# sensors.net
KiCad netlist of a schematic drawn in Altium Designer
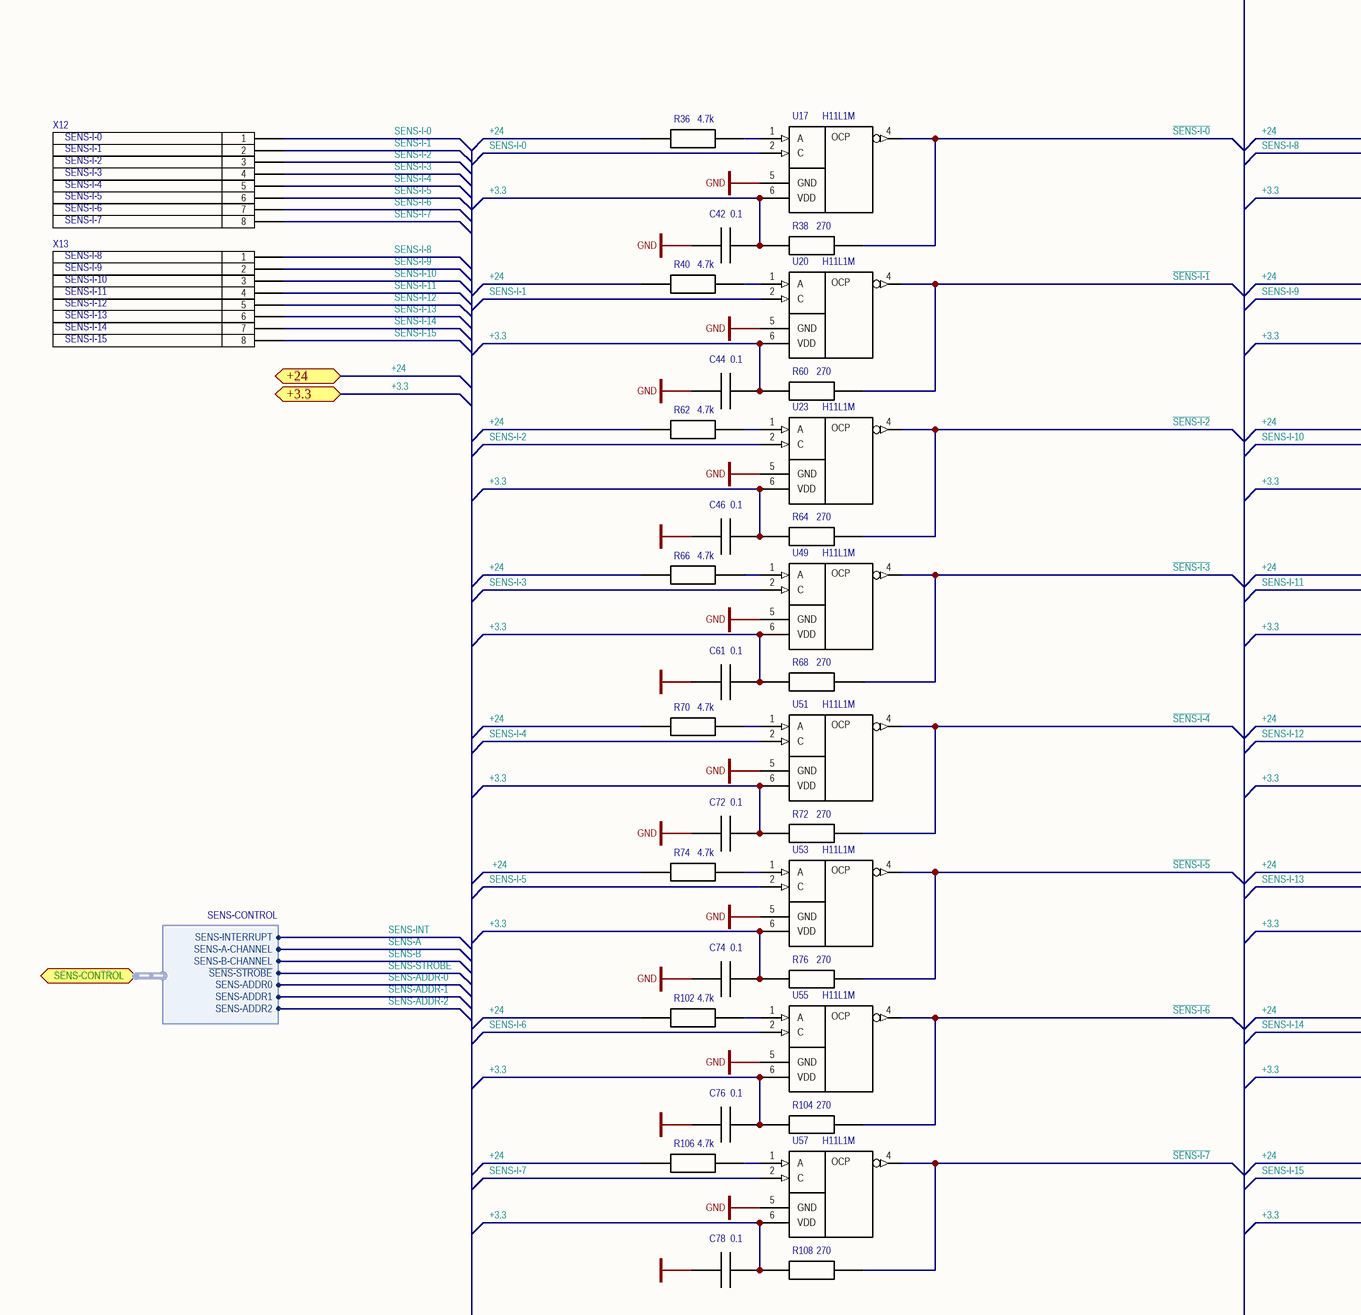
[diagram p0: sensors.SchDoc, top left]
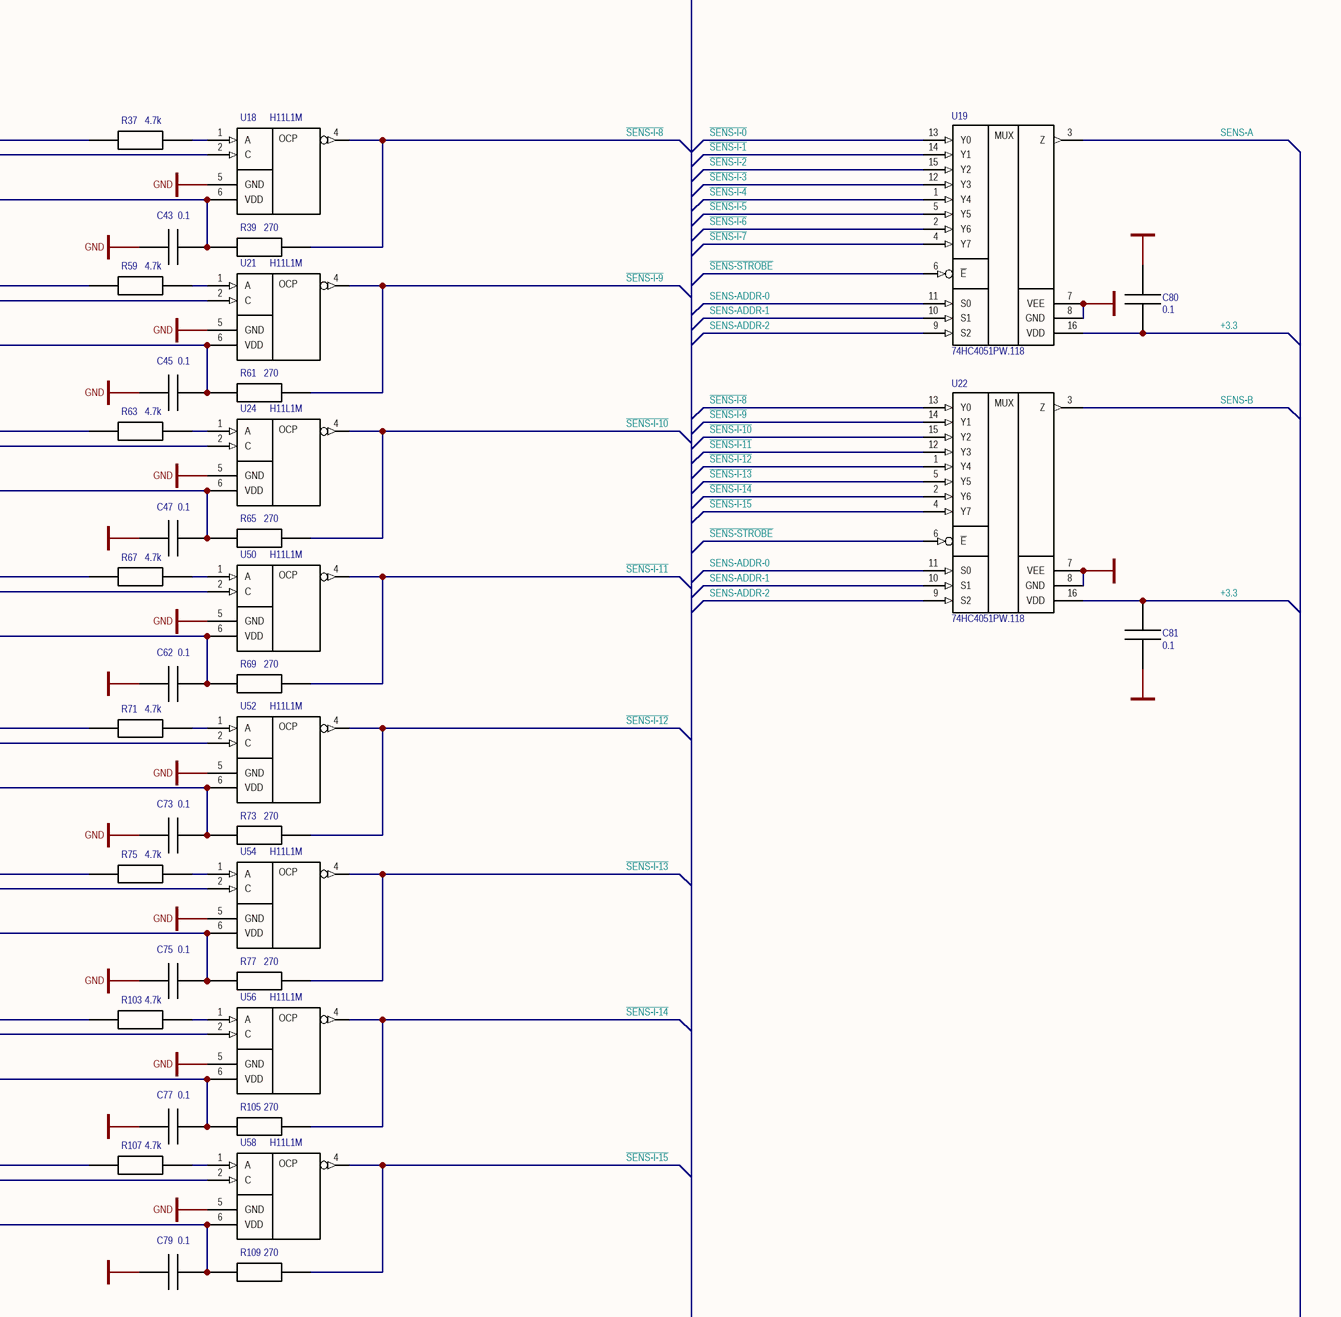
[diagram p1: sensors.SchDoc, top right]
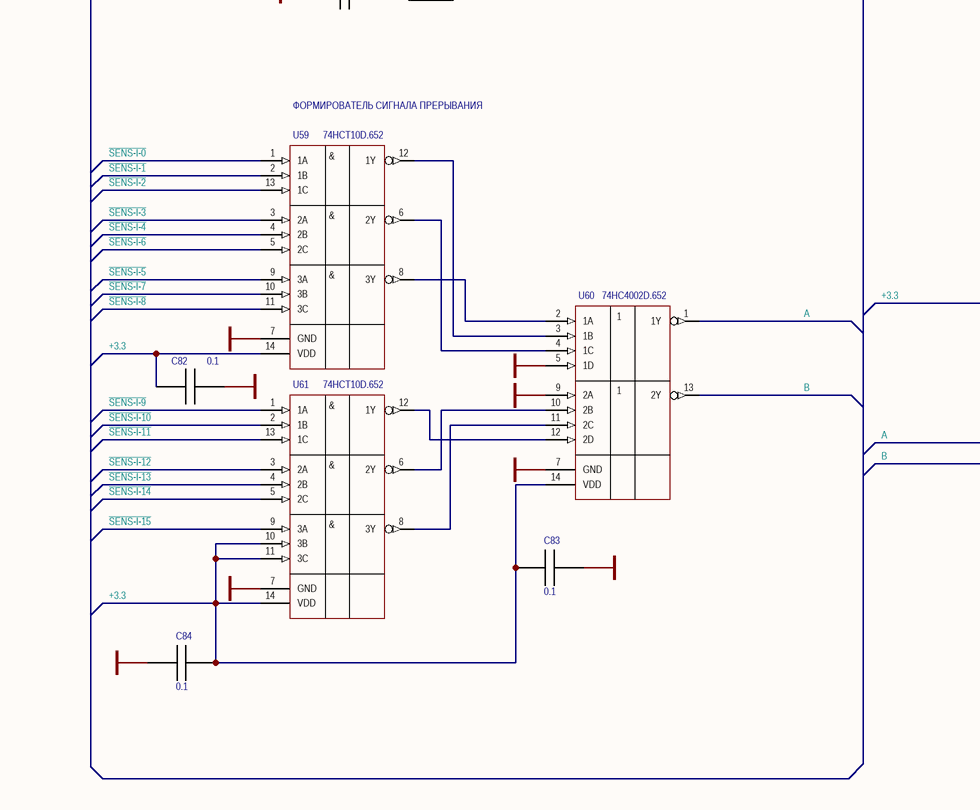
[diagram p2: sensors.SchDoc, bottom left]
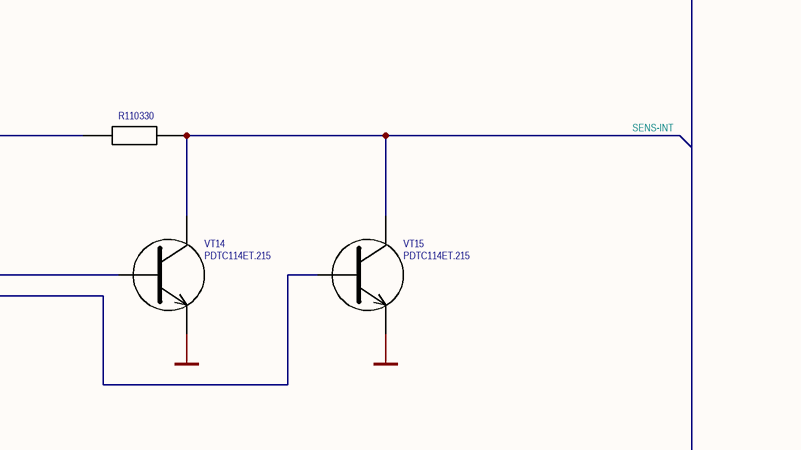
[diagram p3: sensors.SchDoc, bottom right]

(export (version "E")
  (design (tool "Eeschema 10.0.6"))
  (components
    (comp (ref "C42")
      (value "0.1")
      (footprint "CAPC2012X04N")
      (description "SMD конденсатор")
      (libsource (lib "ulysses_library") (part "C"))
    )
    (comp (ref "C43")
      (value "0.1")
      (footprint "CAPC2012X04N")
      (description "SMD конденсатор")
      (libsource (lib "ulysses_library") (part "C"))
    )
    (comp (ref "C44")
      (value "0.1")
      (footprint "CAPC2012X04N")
      (description "SMD конденсатор")
      (libsource (lib "ulysses_library") (part "C"))
    )
    (comp (ref "C45")
      (value "0.1")
      (footprint "CAPC2012X04N")
      (description "SMD конденсатор")
      (libsource (lib "ulysses_library") (part "C"))
    )
    (comp (ref "C46")
      (value "0.1")
      (footprint "CAPC2012X04N")
      (description "SMD конденсатор")
      (libsource (lib "ulysses_library") (part "C"))
    )
    (comp (ref "C47")
      (value "0.1")
      (footprint "CAPC2012X04N")
      (description "SMD конденсатор")
      (libsource (lib "ulysses_library") (part "C"))
    )
    (comp (ref "C61")
      (value "0.1")
      (footprint "CAPC2012X04N")
      (description "SMD конденсатор")
      (libsource (lib "ulysses_library") (part "C"))
    )
    (comp (ref "C62")
      (value "0.1")
      (footprint "CAPC2012X04N")
      (description "SMD конденсатор")
      (libsource (lib "ulysses_library") (part "C"))
    )
    (comp (ref "C72")
      (value "0.1")
      (footprint "CAPC2012X04N")
      (description "SMD конденсатор")
      (libsource (lib "ulysses_library") (part "C"))
    )
    (comp (ref "C73")
      (value "0.1")
      (footprint "CAPC2012X04N")
      (description "SMD конденсатор")
      (libsource (lib "ulysses_library") (part "C"))
    )
    (comp (ref "C74")
      (value "0.1")
      (footprint "CAPC2012X04N")
      (description "SMD конденсатор")
      (libsource (lib "ulysses_library") (part "C"))
    )
    (comp (ref "C75")
      (value "0.1")
      (footprint "CAPC2012X04N")
      (description "SMD конденсатор")
      (libsource (lib "ulysses_library") (part "C"))
    )
    (comp (ref "C76")
      (value "0.1")
      (footprint "CAPC2012X04N")
      (description "SMD конденсатор")
      (libsource (lib "ulysses_library") (part "C"))
    )
    (comp (ref "C77")
      (value "0.1")
      (footprint "CAPC2012X04N")
      (description "SMD конденсатор")
      (libsource (lib "ulysses_library") (part "C"))
    )
    (comp (ref "C78")
      (value "0.1")
      (footprint "CAPC2012X04N")
      (description "SMD конденсатор")
      (libsource (lib "ulysses_library") (part "C"))
    )
    (comp (ref "C79")
      (value "0.1")
      (footprint "CAPC2012X04N")
      (description "SMD конденсатор")
      (libsource (lib "ulysses_library") (part "C"))
    )
    (comp (ref "C80")
      (value "0.1")
      (footprint "CAPC2012X04N")
      (description "SMD конденсатор")
      (libsource (lib "ulysses_library") (part "C"))
    )
    (comp (ref "C81")
      (value "0.1")
      (footprint "CAPC2012X04N")
      (description "SMD конденсатор")
      (libsource (lib "") (part "C_1"))
    )
    (comp (ref "C82")
      (value "0.1")
      (footprint "CAPC2012X04N")
      (description "SMD конденсатор")
      (libsource (lib "ulysses_library") (part "C"))
    )
    (comp (ref "C83")
      (value "0.1")
      (footprint "CAPC2012X04N")
      (description "SMD конденсатор")
      (libsource (lib "ulysses_library") (part "C"))
    )
    (comp (ref "C84")
      (value "0.1")
      (footprint "CAPC2012X04N")
      (description "SMD конденсатор")
      (libsource (lib "ulysses_library") (part "C"))
    )
    (comp (ref "R36")
      (value "4.7k")
      (footprint "RESC2012X04N")
      (description "SMD резистор")
      (libsource (lib "") (part "R_1"))
    )
    (comp (ref "R37")
      (value "4.7k")
      (footprint "RESC2012X04N")
      (description "SMD резистор")
      (libsource (lib "ulysses_library") (part "R"))
    )
    (comp (ref "R38")
      (value "270")
      (footprint "RESC2012X04N")
      (description "SMD резистор")
      (libsource (lib "") (part "R_1"))
    )
    (comp (ref "R39")
      (value "270")
      (footprint "RESC2012X04N")
      (description "SMD резистор")
      (libsource (lib "") (part "R_1"))
    )
    (comp (ref "R40")
      (value "4.7k")
      (footprint "RESC2012X04N")
      (description "SMD резистор")
      (libsource (lib "") (part "R_1"))
    )
    (comp (ref "R59")
      (value "4.7k")
      (footprint "RESC2012X04N")
      (description "SMD резистор")
      (libsource (lib "ulysses_library") (part "R"))
    )
    (comp (ref "R60")
      (value "270")
      (footprint "RESC2012X04N")
      (description "SMD резистор")
      (libsource (lib "") (part "R_1"))
    )
    (comp (ref "R61")
      (value "270")
      (footprint "RESC2012X04N")
      (description "SMD резистор")
      (libsource (lib "") (part "R_1"))
    )
    (comp (ref "R62")
      (value "4.7k")
      (footprint "RESC2012X04N")
      (description "SMD резистор")
      (libsource (lib "") (part "R_1"))
    )
    (comp (ref "R63")
      (value "4.7k")
      (footprint "RESC2012X04N")
      (description "SMD резистор")
      (libsource (lib "ulysses_library") (part "R"))
    )
    (comp (ref "R64")
      (value "270")
      (footprint "RESC2012X04N")
      (description "SMD резистор")
      (libsource (lib "") (part "R_1"))
    )
    (comp (ref "R65")
      (value "270")
      (footprint "RESC2012X04N")
      (description "SMD резистор")
      (libsource (lib "") (part "R_1"))
    )
    (comp (ref "R66")
      (value "4.7k")
      (footprint "RESC2012X04N")
      (description "SMD резистор")
      (libsource (lib "") (part "R_1"))
    )
    (comp (ref "R67")
      (value "4.7k")
      (footprint "RESC2012X04N")
      (description "SMD резистор")
      (libsource (lib "ulysses_library") (part "R"))
    )
    (comp (ref "R68")
      (value "270")
      (footprint "RESC2012X04N")
      (description "SMD резистор")
      (libsource (lib "") (part "R_1"))
    )
    (comp (ref "R69")
      (value "270")
      (footprint "RESC2012X04N")
      (description "SMD резистор")
      (libsource (lib "") (part "R_1"))
    )
    (comp (ref "R70")
      (value "4.7k")
      (footprint "RESC2012X04N")
      (description "SMD резистор")
      (libsource (lib "") (part "R_1"))
    )
    (comp (ref "R71")
      (value "4.7k")
      (footprint "RESC2012X04N")
      (description "SMD резистор")
      (libsource (lib "ulysses_library") (part "R"))
    )
    (comp (ref "R72")
      (value "270")
      (footprint "RESC2012X04N")
      (description "SMD резистор")
      (libsource (lib "") (part "R_1"))
    )
    (comp (ref "R73")
      (value "270")
      (footprint "RESC2012X04N")
      (description "SMD резистор")
      (libsource (lib "") (part "R_1"))
    )
    (comp (ref "R74")
      (value "4.7k")
      (footprint "RESC2012X04N")
      (description "SMD резистор")
      (libsource (lib "") (part "R_1"))
    )
    (comp (ref "R75")
      (value "4.7k")
      (footprint "RESC2012X04N")
      (description "SMD резистор")
      (libsource (lib "ulysses_library") (part "R"))
    )
    (comp (ref "R76")
      (value "270")
      (footprint "RESC2012X04N")
      (description "SMD резистор")
      (libsource (lib "") (part "R_1"))
    )
    (comp (ref "R77")
      (value "270")
      (footprint "RESC2012X04N")
      (description "SMD резистор")
      (libsource (lib "") (part "R_1"))
    )
    (comp (ref "R102")
      (value "4.7k")
      (footprint "RESC2012X04N")
      (description "SMD резистор")
      (libsource (lib "") (part "R_1"))
    )
    (comp (ref "R103")
      (value "4.7k")
      (footprint "RESC2012X04N")
      (description "SMD резистор")
      (libsource (lib "ulysses_library") (part "R"))
    )
    (comp (ref "R104")
      (value "270")
      (footprint "RESC2012X04N")
      (description "SMD резистор")
      (libsource (lib "") (part "R_1"))
    )
    (comp (ref "R105")
      (value "270")
      (footprint "RESC2012X04N")
      (description "SMD резистор")
      (libsource (lib "") (part "R_1"))
    )
    (comp (ref "R106")
      (value "4.7k")
      (footprint "RESC2012X04N")
      (description "SMD резистор")
      (libsource (lib "") (part "R_1"))
    )
    (comp (ref "R107")
      (value "4.7k")
      (footprint "RESC2012X04N")
      (description "SMD резистор")
      (libsource (lib "ulysses_library") (part "R"))
    )
    (comp (ref "R108")
      (value "270")
      (footprint "RESC2012X04N")
      (description "SMD резистор")
      (libsource (lib "") (part "R_1"))
    )
    (comp (ref "R109")
      (value "270")
      (footprint "RESC2012X04N")
      (description "SMD резистор")
      (libsource (lib "") (part "R_1"))
    )
    (comp (ref "R110")
      (value "330")
      (footprint "RESC3216X05N")
      (description "SMD резистор")
      (libsource (lib "ulysses_library") (part "R"))
    )
    (comp (ref "U17")
      (value "H11L1M")
      (footprint "DIP6")
      (description "Fairchild H11L1M Schmitt Trigger Output Optocoupler")
      (libsource (lib "") (part "H11L1M_1"))
    )
    (comp (ref "U18")
      (value "H11L1M")
      (footprint "DIP6")
      (description "Fairchild H11L1M Schmitt Trigger Output Optocoupler")
      (libsource (lib "") (part "H11L1M_1"))
    )
    (comp (ref "U19")
      (value "74HC4051PW.118")
      (footprint "TSOP65P640X120-16N")
      (libsource (lib "ulysses_library") (part "74HC4051PW.118"))
    )
    (comp (ref "U20")
      (value "H11L1M")
      (footprint "DIP6")
      (description "Fairchild H11L1M Schmitt Trigger Output Optocoupler")
      (libsource (lib "") (part "H11L1M_1"))
    )
    (comp (ref "U21")
      (value "H11L1M")
      (footprint "DIP6")
      (description "Fairchild H11L1M Schmitt Trigger Output Optocoupler")
      (libsource (lib "") (part "H11L1M_1"))
    )
    (comp (ref "U22")
      (value "74HC4051PW.118")
      (footprint "TSOP65P640X120-16N")
      (libsource (lib "ulysses_library") (part "74HC4051PW.118"))
    )
    (comp (ref "U23")
      (value "H11L1M")
      (footprint "DIP6")
      (description "Fairchild H11L1M Schmitt Trigger Output Optocoupler")
      (libsource (lib "") (part "H11L1M_1"))
    )
    (comp (ref "U24")
      (value "H11L1M")
      (footprint "DIP6")
      (description "Fairchild H11L1M Schmitt Trigger Output Optocoupler")
      (libsource (lib "") (part "H11L1M_1"))
    )
    (comp (ref "U49")
      (value "H11L1M")
      (footprint "DIP6")
      (description "Fairchild H11L1M Schmitt Trigger Output Optocoupler")
      (libsource (lib "ulysses_library") (part "H11L1M"))
    )
    (comp (ref "U50")
      (value "H11L1M")
      (footprint "DIP6")
      (description "Fairchild H11L1M Schmitt Trigger Output Optocoupler")
      (libsource (lib "ulysses_library") (part "H11L1M"))
    )
    (comp (ref "U51")
      (value "H11L1M")
      (footprint "DIP6")
      (description "Fairchild H11L1M Schmitt Trigger Output Optocoupler")
      (libsource (lib "") (part "H11L1M_1"))
    )
    (comp (ref "U52")
      (value "H11L1M")
      (footprint "DIP6")
      (description "Fairchild H11L1M Schmitt Trigger Output Optocoupler")
      (libsource (lib "") (part "H11L1M_1"))
    )
    (comp (ref "U53")
      (value "H11L1M")
      (footprint "DIP6")
      (description "Fairchild H11L1M Schmitt Trigger Output Optocoupler")
      (libsource (lib "") (part "H11L1M_1"))
    )
    (comp (ref "U54")
      (value "H11L1M")
      (footprint "DIP6")
      (description "Fairchild H11L1M Schmitt Trigger Output Optocoupler")
      (libsource (lib "") (part "H11L1M_1"))
    )
    (comp (ref "U55")
      (value "H11L1M")
      (footprint "DIP6")
      (description "Fairchild H11L1M Schmitt Trigger Output Optocoupler")
      (libsource (lib "") (part "H11L1M_1"))
    )
    (comp (ref "U56")
      (value "H11L1M")
      (footprint "DIP6")
      (description "Fairchild H11L1M Schmitt Trigger Output Optocoupler")
      (libsource (lib "") (part "H11L1M_1"))
    )
    (comp (ref "U57")
      (value "H11L1M")
      (footprint "DIP6")
      (description "Fairchild H11L1M Schmitt Trigger Output Optocoupler")
      (libsource (lib "") (part "H11L1M_1"))
    )
    (comp (ref "U58")
      (value "H11L1M")
      (footprint "DIP6")
      (description "Fairchild H11L1M Schmitt Trigger Output Optocoupler")
      (libsource (lib "") (part "H11L1M_1"))
    )
    (comp (ref "U59")
      (value "74HCT10D.652")
      (footprint "SOIC127P600X175-14N")
      (libsource (lib "ulysses_library") (part "74HCT10D.652"))
    )
    (comp (ref "U60")
      (value "74HC4002D.652")
      (footprint "SOIC127P600X175-14N")
      (libsource (lib "ulysses_library") (part "74HC4002D.652"))
    )
    (comp (ref "U61")
      (value "74HCT10D.652")
      (footprint "SOIC127P600X175-14N")
      (libsource (lib "ulysses_library") (part "74HCT10D.652"))
    )
    (comp (ref "VT14")
      (value "PDTC114ET.215")
      (footprint "SOT95P238X102-3N")
      (description "NPN transistor with bias circuit")
      (libsource (lib "ulysses_library") (part "PDTC114ET.215"))
    )
    (comp (ref "VT15")
      (value "PDTC114ET.215")
      (footprint "SOT95P238X102-3N")
      (description "NPN transistor with bias circuit")
      (libsource (lib "") (part "PDTC114ET.215_1"))
    )
    (comp (ref "X12")
      (value "MINI-FIT-8-WAY-M")
      (footprint "MINI-FIT-8-WAY-SM")
      (libsource (lib "ulysses_library") (part "MINI-FIT-8-WAY-M"))
    )
    (comp (ref "X13")
      (value "MINI-FIT-8-WAY-M")
      (footprint "MINI-FIT-8-WAY-SM")
      (libsource (lib "ulysses_library") (part "MINI-FIT-8-WAY-M"))
    )
  )
  (nets
    (net (code "2") (name "/+3.3") (class "Default")
      (node (ref "C42") (pin "2") (pinfunction "2_2") (pintype "passive"))
      (node (ref "C43") (pin "2") (pinfunction "2_2") (pintype "passive"))
      (node (ref "C44") (pin "2") (pinfunction "2_2") (pintype "passive"))
      (node (ref "C45") (pin "2") (pinfunction "2_2") (pintype "passive"))
      (node (ref "C46") (pin "2") (pinfunction "2_2") (pintype "passive"))
      (node (ref "C47") (pin "2") (pinfunction "2_2") (pintype "passive"))
      (node (ref "C61") (pin "2") (pinfunction "2_2") (pintype "passive"))
      (node (ref "C62") (pin "2") (pinfunction "2_2") (pintype "passive"))
      (node (ref "C72") (pin "2") (pinfunction "2_2") (pintype "passive"))
      (node (ref "C73") (pin "2") (pinfunction "2_2") (pintype "passive"))
      (node (ref "C74") (pin "2") (pinfunction "2_2") (pintype "passive"))
      (node (ref "C75") (pin "2") (pinfunction "2_2") (pintype "passive"))
      (node (ref "C76") (pin "2") (pinfunction "2_2") (pintype "passive"))
      (node (ref "C77") (pin "2") (pinfunction "2_2") (pintype "passive"))
      (node (ref "C78") (pin "2") (pinfunction "2_2") (pintype "passive"))
      (node (ref "C79") (pin "2") (pinfunction "2_2") (pintype "passive"))
      (node (ref "C80") (pin "1") (pinfunction "1_1") (pintype "passive"))
      (node (ref "C81") (pin "2") (pinfunction "2_2") (pintype "passive"))
      (node (ref "C82") (pin "1") (pinfunction "1_1") (pintype "passive"))
      (node (ref "C83") (pin "1") (pinfunction "1_1") (pintype "passive"))
      (node (ref "C84") (pin "2") (pinfunction "2_2") (pintype "passive"))
      (node (ref "R104") (pin "1") (pintype "passive"))
      (node (ref "R105") (pin "1") (pintype "passive"))
      (node (ref "R108") (pin "1") (pintype "passive"))
      (node (ref "R109") (pin "1") (pintype "passive"))
      (node (ref "R110") (pin "1") (pintype "passive"))
      (node (ref "R38") (pin "1") (pintype "passive"))
      (node (ref "R39") (pin "1") (pintype "passive"))
      (node (ref "R60") (pin "1") (pintype "passive"))
      (node (ref "R61") (pin "1") (pintype "passive"))
      (node (ref "R64") (pin "1") (pintype "passive"))
      (node (ref "R65") (pin "1") (pintype "passive"))
      (node (ref "R68") (pin "1") (pintype "passive"))
      (node (ref "R69") (pin "1") (pintype "passive"))
      (node (ref "R72") (pin "1") (pintype "passive"))
      (node (ref "R73") (pin "1") (pintype "passive"))
      (node (ref "R76") (pin "1") (pintype "passive"))
      (node (ref "R77") (pin "1") (pintype "passive"))
      (node (ref "U17") (pin "6") (pinfunction "VDD_6") (pintype "power_in"))
      (node (ref "U18") (pin "6") (pinfunction "VDD_6") (pintype "power_in"))
      (node (ref "U19") (pin "16") (pinfunction "VDD_16") (pintype "power_in"))
      (node (ref "U20") (pin "6") (pinfunction "VDD_6") (pintype "power_in"))
      (node (ref "U21") (pin "6") (pinfunction "VDD_6") (pintype "power_in"))
      (node (ref "U22") (pin "16") (pinfunction "VDD_16") (pintype "power_in"))
      (node (ref "U23") (pin "6") (pinfunction "VDD_6") (pintype "power_in"))
      (node (ref "U24") (pin "6") (pinfunction "VDD_6") (pintype "power_in"))
      (node (ref "U49") (pin "6") (pinfunction "VDD_6") (pintype "power_in"))
      (node (ref "U50") (pin "6") (pinfunction "VDD_6") (pintype "power_in"))
      (node (ref "U51") (pin "6") (pinfunction "VDD_6") (pintype "power_in"))
      (node (ref "U52") (pin "6") (pinfunction "VDD_6") (pintype "power_in"))
      (node (ref "U53") (pin "6") (pinfunction "VDD_6") (pintype "power_in"))
      (node (ref "U54") (pin "6") (pinfunction "VDD_6") (pintype "power_in"))
      (node (ref "U55") (pin "6") (pinfunction "VDD_6") (pintype "power_in"))
      (node (ref "U56") (pin "6") (pinfunction "VDD_6") (pintype "power_in"))
      (node (ref "U57") (pin "6") (pinfunction "VDD_6") (pintype "power_in"))
      (node (ref "U58") (pin "6") (pinfunction "VDD_6") (pintype "power_in"))
      (node (ref "U59") (pin "14") (pinfunction "VDD_14") (pintype "power_in"))
      (node (ref "U60") (pin "14") (pinfunction "VDD_14") (pintype "power_in"))
      (node (ref "U61") (pin "10") (pinfunction "3B_10") (pintype "input"))
      (node (ref "U61") (pin "11") (pinfunction "3C_11") (pintype "input"))
      (node (ref "U61") (pin "14") (pinfunction "VDD_14") (pintype "power_in"))
    )
    (net (code "3") (name "/+24") (class "Default")
      (node (ref "R102") (pin "1") (pintype "passive"))
      (node (ref "R103") (pin "1") (pintype "passive"))
      (node (ref "R106") (pin "1") (pintype "passive"))
      (node (ref "R107") (pin "1") (pintype "passive"))
      (node (ref "R36") (pin "1") (pintype "passive"))
      (node (ref "R37") (pin "1") (pintype "passive"))
      (node (ref "R40") (pin "1") (pintype "passive"))
      (node (ref "R59") (pin "1") (pintype "passive"))
      (node (ref "R62") (pin "1") (pintype "passive"))
      (node (ref "R63") (pin "1") (pintype "passive"))
      (node (ref "R66") (pin "1") (pintype "passive"))
      (node (ref "R67") (pin "1") (pintype "passive"))
      (node (ref "R70") (pin "1") (pintype "passive"))
      (node (ref "R71") (pin "1") (pintype "passive"))
      (node (ref "R74") (pin "1") (pintype "passive"))
      (node (ref "R75") (pin "1") (pintype "passive"))
    )
    (net (code "4") (name "/A") (class "Default")
      (node (ref "U60") (pin "1") (pinfunction "1Y_1") (pintype "output"))
      (node (ref "VT14") (pin "1") (pinfunction "B_1") (pintype "power_in"))
    )
    (net (code "5") (name "/B") (class "Default")
      (node (ref "U60") (pin "13") (pinfunction "2Y_13") (pintype "output"))
      (node (ref "VT15") (pin "1") (pinfunction "B_1") (pintype "power_in"))
    )
    (net (code "6") (name "/SENS-A") (class "Default")
      (node (ref "U19") (pin "3") (pinfunction "Z_3") (pintype "output"))
    )
    (net (code "7") (name "/SENS-ADDR-0") (class "Default")
      (node (ref "U19") (pin "11") (pinfunction "S0_11") (pintype "input"))
      (node (ref "U22") (pin "11") (pinfunction "S0_11") (pintype "input"))
    )
    (net (code "8") (name "/SENS-ADDR-1") (class "Default")
      (node (ref "U19") (pin "10") (pinfunction "S1_10") (pintype "input"))
      (node (ref "U22") (pin "10") (pinfunction "S1_10") (pintype "input"))
    )
    (net (code "9") (name "/SENS-ADDR-2") (class "Default")
      (node (ref "U19") (pin "9") (pinfunction "S2_9") (pintype "input"))
      (node (ref "U22") (pin "9") (pinfunction "S2_9") (pintype "input"))
    )
    (net (code "10") (name "/SENS-B") (class "Default")
      (node (ref "U22") (pin "3") (pinfunction "Z_3") (pintype "output"))
    )
    (net (code "11") (name "/SENS-I-0") (class "Default")
      (node (ref "U17") (pin "2") (pinfunction "C_2") (pintype "input"))
      (node (ref "X12") (pin "1") (pinfunction "1_1") (pintype "passive"))
    )
    (net (code "12") (name "/SENS-I-1") (class "Default")
      (node (ref "U20") (pin "2") (pinfunction "C_2") (pintype "input"))
      (node (ref "X12") (pin "2") (pinfunction "2_2") (pintype "passive"))
    )
    (net (code "13") (name "/SENS-I-2") (class "Default")
      (node (ref "U23") (pin "2") (pinfunction "C_2") (pintype "input"))
      (node (ref "X12") (pin "3") (pinfunction "3_3") (pintype "passive"))
    )
    (net (code "14") (name "/SENS-I-3") (class "Default")
      (node (ref "U49") (pin "2") (pinfunction "C_2") (pintype "input"))
      (node (ref "X12") (pin "4") (pinfunction "4_4") (pintype "passive"))
    )
    (net (code "15") (name "/SENS-I-4") (class "Default")
      (node (ref "U51") (pin "2") (pinfunction "C_2") (pintype "input"))
      (node (ref "X12") (pin "5") (pinfunction "5_5") (pintype "passive"))
    )
    (net (code "16") (name "/SENS-I-5") (class "Default")
      (node (ref "U53") (pin "2") (pinfunction "C_2") (pintype "input"))
      (node (ref "X12") (pin "6") (pinfunction "6_6") (pintype "passive"))
    )
    (net (code "17") (name "/SENS-I-6") (class "Default")
      (node (ref "U55") (pin "2") (pinfunction "C_2") (pintype "input"))
      (node (ref "X12") (pin "7") (pinfunction "7_7") (pintype "passive"))
    )
    (net (code "18") (name "/SENS-I-7") (class "Default")
      (node (ref "U57") (pin "2") (pinfunction "C_2") (pintype "input"))
      (node (ref "X12") (pin "8") (pinfunction "8_8") (pintype "passive"))
    )
    (net (code "19") (name "/SENS-I-8") (class "Default")
      (node (ref "U18") (pin "2") (pinfunction "C_2") (pintype "input"))
      (node (ref "X13") (pin "1") (pinfunction "1_1") (pintype "passive"))
    )
    (net (code "20") (name "/SENS-I-9") (class "Default")
      (node (ref "U21") (pin "2") (pinfunction "C_2") (pintype "input"))
      (node (ref "X13") (pin "2") (pinfunction "2_2") (pintype "passive"))
    )
    (net (code "21") (name "/SENS-I-10") (class "Default")
      (node (ref "U24") (pin "2") (pinfunction "C_2") (pintype "input"))
      (node (ref "X13") (pin "3") (pinfunction "3_3") (pintype "passive"))
    )
    (net (code "22") (name "/SENS-I-11") (class "Default")
      (node (ref "U50") (pin "2") (pinfunction "C_2") (pintype "input"))
      (node (ref "X13") (pin "4") (pinfunction "4_4") (pintype "passive"))
    )
    (net (code "23") (name "/SENS-I-12") (class "Default")
      (node (ref "U52") (pin "2") (pinfunction "C_2") (pintype "input"))
      (node (ref "X13") (pin "5") (pinfunction "5_5") (pintype "passive"))
    )
    (net (code "24") (name "/SENS-I-13") (class "Default")
      (node (ref "U54") (pin "2") (pinfunction "C_2") (pintype "input"))
      (node (ref "X13") (pin "6") (pinfunction "6_6") (pintype "passive"))
    )
    (net (code "25") (name "/SENS-I-14") (class "Default")
      (node (ref "U56") (pin "2") (pinfunction "C_2") (pintype "input"))
      (node (ref "X13") (pin "7") (pinfunction "7_7") (pintype "passive"))
    )
    (net (code "26") (name "/SENS-I-15") (class "Default")
      (node (ref "U58") (pin "2") (pinfunction "C_2") (pintype "input"))
      (node (ref "X13") (pin "8") (pinfunction "8_8") (pintype "passive"))
    )
    (net (code "27") (name "/SENS-INT") (class "Default")
      (node (ref "R110") (pin "2") (pinfunction "2_2") (pintype "passive"))
      (node (ref "VT14") (pin "3") (pinfunction "C_3") (pintype "power_in"))
      (node (ref "VT15") (pin "3") (pinfunction "C_3") (pintype "power_in"))
    )
    (net (code "29") (name "/~{SENS-I-0}") (class "Default")
      (node (ref "R38") (pin "2") (pinfunction "2_2") (pintype "passive"))
      (node (ref "U17") (pin "4") (pinfunction "OUT_4") (pintype "output"))
      (node (ref "U19") (pin "13") (pinfunction "Y0_13") (pintype "input"))
      (node (ref "U59") (pin "1") (pinfunction "1A_1") (pintype "input"))
    )
    (net (code "30") (name "/~{SENS-I-1}") (class "Default")
      (node (ref "R60") (pin "2") (pinfunction "2_2") (pintype "passive"))
      (node (ref "U19") (pin "14") (pinfunction "Y1_14") (pintype "input"))
      (node (ref "U20") (pin "4") (pinfunction "OUT_4") (pintype "output"))
      (node (ref "U59") (pin "2") (pinfunction "1B_2") (pintype "input"))
    )
    (net (code "31") (name "/~{SENS-I-2}") (class "Default")
      (node (ref "R64") (pin "2") (pinfunction "2_2") (pintype "passive"))
      (node (ref "U19") (pin "15") (pinfunction "Y2_15") (pintype "input"))
      (node (ref "U23") (pin "4") (pinfunction "OUT_4") (pintype "output"))
      (node (ref "U59") (pin "13") (pinfunction "1C_13") (pintype "input"))
    )
    (net (code "32") (name "/~{SENS-I-3}") (class "Default")
      (node (ref "R68") (pin "2") (pinfunction "2_2") (pintype "passive"))
      (node (ref "U19") (pin "12") (pinfunction "Y3_12") (pintype "input"))
      (node (ref "U49") (pin "4") (pinfunction "OUT_4") (pintype "output"))
      (node (ref "U59") (pin "3") (pinfunction "2A_3") (pintype "input"))
    )
    (net (code "33") (name "/~{SENS-I-4}") (class "Default")
      (node (ref "R72") (pin "2") (pinfunction "2_2") (pintype "passive"))
      (node (ref "U19") (pin "1") (pinfunction "Y4_1") (pintype "input"))
      (node (ref "U51") (pin "4") (pinfunction "OUT_4") (pintype "output"))
      (node (ref "U59") (pin "4") (pinfunction "2B_4") (pintype "input"))
    )
    (net (code "34") (name "/~{SENS-I-5}") (class "Default")
      (node (ref "R76") (pin "2") (pinfunction "2_2") (pintype "passive"))
      (node (ref "U19") (pin "5") (pinfunction "Y5_5") (pintype "input"))
      (node (ref "U53") (pin "4") (pinfunction "OUT_4") (pintype "output"))
      (node (ref "U59") (pin "9") (pinfunction "3A_9") (pintype "input"))
    )
    (net (code "35") (name "/~{SENS-I-6}") (class "Default")
      (node (ref "R104") (pin "2") (pinfunction "2_2") (pintype "passive"))
      (node (ref "U19") (pin "2") (pinfunction "Y6_2") (pintype "input"))
      (node (ref "U55") (pin "4") (pinfunction "OUT_4") (pintype "output"))
      (node (ref "U59") (pin "5") (pinfunction "2C_5") (pintype "input"))
    )
    (net (code "36") (name "/~{SENS-I-7}") (class "Default")
      (node (ref "R108") (pin "2") (pinfunction "2_2") (pintype "passive"))
      (node (ref "U19") (pin "4") (pinfunction "Y7_4") (pintype "input"))
      (node (ref "U57") (pin "4") (pinfunction "OUT_4") (pintype "output"))
      (node (ref "U59") (pin "10") (pinfunction "3B_10") (pintype "input"))
    )
    (net (code "37") (name "/~{SENS-I-8}") (class "Default")
      (node (ref "R39") (pin "2") (pinfunction "2_2") (pintype "passive"))
      (node (ref "U18") (pin "4") (pinfunction "OUT_4") (pintype "output"))
      (node (ref "U22") (pin "13") (pinfunction "Y0_13") (pintype "input"))
      (node (ref "U59") (pin "11") (pinfunction "3C_11") (pintype "input"))
    )
    (net (code "38") (name "/~{SENS-I-9}") (class "Default")
      (node (ref "R61") (pin "2") (pinfunction "2_2") (pintype "passive"))
      (node (ref "U21") (pin "4") (pinfunction "OUT_4") (pintype "output"))
      (node (ref "U22") (pin "14") (pinfunction "Y1_14") (pintype "input"))
      (node (ref "U61") (pin "1") (pinfunction "1A_1") (pintype "input"))
    )
    (net (code "39") (name "/~{SENS-I-10}") (class "Default")
      (node (ref "R65") (pin "2") (pinfunction "2_2") (pintype "passive"))
      (node (ref "U22") (pin "15") (pinfunction "Y2_15") (pintype "input"))
      (node (ref "U24") (pin "4") (pinfunction "OUT_4") (pintype "output"))
      (node (ref "U61") (pin "2") (pinfunction "1B_2") (pintype "input"))
    )
    (net (code "40") (name "/~{SENS-I-11}") (class "Default")
      (node (ref "R69") (pin "2") (pinfunction "2_2") (pintype "passive"))
      (node (ref "U22") (pin "12") (pinfunction "Y3_12") (pintype "input"))
      (node (ref "U50") (pin "4") (pinfunction "OUT_4") (pintype "output"))
      (node (ref "U61") (pin "13") (pinfunction "1C_13") (pintype "input"))
    )
    (net (code "41") (name "/~{SENS-I-12}") (class "Default")
      (node (ref "R73") (pin "2") (pinfunction "2_2") (pintype "passive"))
      (node (ref "U22") (pin "1") (pinfunction "Y4_1") (pintype "input"))
      (node (ref "U52") (pin "4") (pinfunction "OUT_4") (pintype "output"))
      (node (ref "U61") (pin "3") (pinfunction "2A_3") (pintype "input"))
    )
    (net (code "42") (name "/~{SENS-I-13}") (class "Default")
      (node (ref "R77") (pin "2") (pinfunction "2_2") (pintype "passive"))
      (node (ref "U22") (pin "5") (pinfunction "Y5_5") (pintype "input"))
      (node (ref "U54") (pin "4") (pinfunction "OUT_4") (pintype "output"))
      (node (ref "U61") (pin "4") (pinfunction "2B_4") (pintype "input"))
    )
    (net (code "43") (name "/~{SENS-I-14}") (class "Default")
      (node (ref "R105") (pin "2") (pinfunction "2_2") (pintype "passive"))
      (node (ref "U22") (pin "2") (pinfunction "Y6_2") (pintype "input"))
      (node (ref "U56") (pin "4") (pinfunction "OUT_4") (pintype "output"))
      (node (ref "U61") (pin "5") (pinfunction "2C_5") (pintype "input"))
    )
    (net (code "44") (name "/~{SENS-I-15}") (class "Default")
      (node (ref "R109") (pin "2") (pinfunction "2_2") (pintype "passive"))
      (node (ref "U22") (pin "4") (pinfunction "Y7_4") (pintype "input"))
      (node (ref "U58") (pin "4") (pinfunction "OUT_4") (pintype "output"))
      (node (ref "U61") (pin "9") (pinfunction "3A_9") (pintype "input"))
    )
    (net (code "45") (name "/~{SENS-STROBE}") (class "Default")
      (node (ref "U19") (pin "6") (pinfunction "~{E}_6") (pintype "input"))
      (node (ref "U22") (pin "6") (pinfunction "~{E}_6") (pintype "input"))
    )
    (net (code "46") (name "GND") (class "Default")
      (node (ref "C42") (pin "1") (pinfunction "1_1") (pintype "passive"))
      (node (ref "C43") (pin "1") (pinfunction "1_1") (pintype "passive"))
      (node (ref "C44") (pin "1") (pinfunction "1_1") (pintype "passive"))
      (node (ref "C45") (pin "1") (pinfunction "1_1") (pintype "passive"))
      (node (ref "C46") (pin "1") (pinfunction "1_1") (pintype "passive"))
      (node (ref "C47") (pin "1") (pinfunction "1_1") (pintype "passive"))
      (node (ref "C61") (pin "1") (pinfunction "1_1") (pintype "passive"))
      (node (ref "C62") (pin "1") (pinfunction "1_1") (pintype "passive"))
      (node (ref "C72") (pin "1") (pinfunction "1_1") (pintype "passive"))
      (node (ref "C73") (pin "1") (pinfunction "1_1") (pintype "passive"))
      (node (ref "C74") (pin "1") (pinfunction "1_1") (pintype "passive"))
      (node (ref "C75") (pin "1") (pinfunction "1_1") (pintype "passive"))
      (node (ref "C76") (pin "1") (pinfunction "1_1") (pintype "passive"))
      (node (ref "C77") (pin "1") (pinfunction "1_1") (pintype "passive"))
      (node (ref "C78") (pin "1") (pinfunction "1_1") (pintype "passive"))
      (node (ref "C79") (pin "1") (pinfunction "1_1") (pintype "passive"))
      (node (ref "C80") (pin "2") (pinfunction "2_2") (pintype "passive"))
      (node (ref "C81") (pin "1") (pinfunction "1_1") (pintype "passive"))
      (node (ref "C82") (pin "2") (pinfunction "2_2") (pintype "passive"))
      (node (ref "C83") (pin "2") (pinfunction "2_2") (pintype "passive"))
      (node (ref "C84") (pin "1") (pinfunction "1_1") (pintype "passive"))
      (node (ref "U17") (pin "5") (pinfunction "GND_5") (pintype "power_in"))
      (node (ref "U18") (pin "5") (pinfunction "GND_5") (pintype "power_in"))
      (node (ref "U19") (pin "7") (pinfunction "VEE_7") (pintype "power_in"))
      (node (ref "U19") (pin "8") (pinfunction "GND_8") (pintype "power_in"))
      (node (ref "U20") (pin "5") (pinfunction "GND_5") (pintype "power_in"))
      (node (ref "U21") (pin "5") (pinfunction "GND_5") (pintype "power_in"))
      (node (ref "U22") (pin "7") (pinfunction "VEE_7") (pintype "power_in"))
      (node (ref "U22") (pin "8") (pinfunction "GND_8") (pintype "power_in"))
      (node (ref "U23") (pin "5") (pinfunction "GND_5") (pintype "power_in"))
      (node (ref "U24") (pin "5") (pinfunction "GND_5") (pintype "power_in"))
      (node (ref "U49") (pin "5") (pinfunction "GND_5") (pintype "power_in"))
      (node (ref "U50") (pin "5") (pinfunction "GND_5") (pintype "power_in"))
      (node (ref "U51") (pin "5") (pinfunction "GND_5") (pintype "power_in"))
      (node (ref "U52") (pin "5") (pinfunction "GND_5") (pintype "power_in"))
      (node (ref "U53") (pin "5") (pinfunction "GND_5") (pintype "power_in"))
      (node (ref "U54") (pin "5") (pinfunction "GND_5") (pintype "power_in"))
      (node (ref "U55") (pin "5") (pinfunction "GND_5") (pintype "power_in"))
      (node (ref "U56") (pin "5") (pinfunction "GND_5") (pintype "power_in"))
      (node (ref "U57") (pin "5") (pinfunction "GND_5") (pintype "power_in"))
      (node (ref "U58") (pin "5") (pinfunction "GND_5") (pintype "power_in"))
      (node (ref "U59") (pin "7") (pinfunction "GND_7") (pintype "power_in"))
      (node (ref "U60") (pin "5") (pinfunction "1D_5") (pintype "input"))
      (node (ref "U60") (pin "7") (pinfunction "GND_7") (pintype "power_in"))
      (node (ref "U60") (pin "9") (pinfunction "2A_9") (pintype "input"))
      (node (ref "U61") (pin "7") (pinfunction "GND_7") (pintype "power_in"))
      (node (ref "VT14") (pin "2") (pinfunction "E_2") (pintype "power_in"))
      (node (ref "VT15") (pin "2") (pinfunction "E_2") (pintype "power_in"))
    )
    (net (code "47") (name "Net-(U17-A)") (class "Default")
      (node (ref "R36") (pin "2") (pinfunction "2_2") (pintype "passive"))
      (node (ref "U17") (pin "1") (pinfunction "A_1") (pintype "input"))
    )
    (net (code "48") (name "Net-(U18-A)") (class "Default")
      (node (ref "R37") (pin "2") (pinfunction "2_2") (pintype "passive"))
      (node (ref "U18") (pin "1") (pinfunction "A_1") (pintype "input"))
    )
    (net (code "49") (name "Net-(U20-A)") (class "Default")
      (node (ref "R40") (pin "2") (pinfunction "2_2") (pintype "passive"))
      (node (ref "U20") (pin "1") (pinfunction "A_1") (pintype "input"))
    )
    (net (code "50") (name "Net-(U21-A)") (class "Default")
      (node (ref "R59") (pin "2") (pinfunction "2_2") (pintype "passive"))
      (node (ref "U21") (pin "1") (pinfunction "A_1") (pintype "input"))
    )
    (net (code "51") (name "Net-(U23-A)") (class "Default")
      (node (ref "R62") (pin "2") (pinfunction "2_2") (pintype "passive"))
      (node (ref "U23") (pin "1") (pinfunction "A_1") (pintype "input"))
    )
    (net (code "52") (name "Net-(U24-A)") (class "Default")
      (node (ref "R63") (pin "2") (pinfunction "2_2") (pintype "passive"))
      (node (ref "U24") (pin "1") (pinfunction "A_1") (pintype "input"))
    )
    (net (code "53") (name "Net-(U49-A)") (class "Default")
      (node (ref "R66") (pin "2") (pinfunction "2_2") (pintype "passive"))
      (node (ref "U49") (pin "1") (pinfunction "A_1") (pintype "input"))
    )
    (net (code "54") (name "Net-(U50-A)") (class "Default")
      (node (ref "R67") (pin "2") (pinfunction "2_2") (pintype "passive"))
      (node (ref "U50") (pin "1") (pinfunction "A_1") (pintype "input"))
    )
    (net (code "55") (name "Net-(U51-A)") (class "Default")
      (node (ref "R70") (pin "2") (pinfunction "2_2") (pintype "passive"))
      (node (ref "U51") (pin "1") (pinfunction "A_1") (pintype "input"))
    )
    (net (code "56") (name "Net-(U52-A)") (class "Default")
      (node (ref "R71") (pin "2") (pinfunction "2_2") (pintype "passive"))
      (node (ref "U52") (pin "1") (pinfunction "A_1") (pintype "input"))
    )
    (net (code "57") (name "Net-(U53-A)") (class "Default")
      (node (ref "R74") (pin "2") (pinfunction "2_2") (pintype "passive"))
      (node (ref "U53") (pin "1") (pinfunction "A_1") (pintype "input"))
    )
    (net (code "58") (name "Net-(U54-A)") (class "Default")
      (node (ref "R75") (pin "2") (pinfunction "2_2") (pintype "passive"))
      (node (ref "U54") (pin "1") (pinfunction "A_1") (pintype "input"))
    )
    (net (code "59") (name "Net-(U55-A)") (class "Default")
      (node (ref "R102") (pin "2") (pinfunction "2_2") (pintype "passive"))
      (node (ref "U55") (pin "1") (pinfunction "A_1") (pintype "input"))
    )
    (net (code "60") (name "Net-(U56-A)") (class "Default")
      (node (ref "R103") (pin "2") (pinfunction "2_2") (pintype "passive"))
      (node (ref "U56") (pin "1") (pinfunction "A_1") (pintype "input"))
    )
    (net (code "61") (name "Net-(U57-A)") (class "Default")
      (node (ref "R106") (pin "2") (pinfunction "2_2") (pintype "passive"))
      (node (ref "U57") (pin "1") (pinfunction "A_1") (pintype "input"))
    )
    (net (code "62") (name "Net-(U58-A)") (class "Default")
      (node (ref "R107") (pin "2") (pinfunction "2_2") (pintype "passive"))
      (node (ref "U58") (pin "1") (pinfunction "A_1") (pintype "input"))
    )
    (net (code "63") (name "Net-(U59-1Y)") (class "Default")
      (node (ref "U59") (pin "12") (pinfunction "1Y_12") (pintype "output"))
      (node (ref "U60") (pin "3") (pinfunction "1B_3") (pintype "input"))
    )
    (net (code "64") (name "Net-(U59-2Y)") (class "Default")
      (node (ref "U59") (pin "6") (pinfunction "2Y_6") (pintype "output"))
      (node (ref "U60") (pin "4") (pinfunction "1C_4") (pintype "input"))
    )
    (net (code "65") (name "Net-(U59-3Y)") (class "Default")
      (node (ref "U59") (pin "8") (pinfunction "3Y_8") (pintype "output"))
      (node (ref "U60") (pin "2") (pinfunction "1A_2") (pintype "input"))
    )
    (net (code "66") (name "Net-(U60-2B)") (class "Default")
      (node (ref "U60") (pin "10") (pinfunction "2B_10") (pintype "input"))
      (node (ref "U61") (pin "6") (pinfunction "2Y_6") (pintype "output"))
    )
    (net (code "67") (name "Net-(U60-2C)") (class "Default")
      (node (ref "U60") (pin "11") (pinfunction "2C_11") (pintype "input"))
      (node (ref "U61") (pin "8") (pinfunction "3Y_8") (pintype "output"))
    )
    (net (code "68") (name "Net-(U60-2D)") (class "Default")
      (node (ref "U60") (pin "12") (pinfunction "2D_12") (pintype "input"))
      (node (ref "U61") (pin "12") (pinfunction "1Y_12") (pintype "output"))
    )
  )
)
